# schematic.net
KiCad netlist of a schematic drawn in EasyEDA
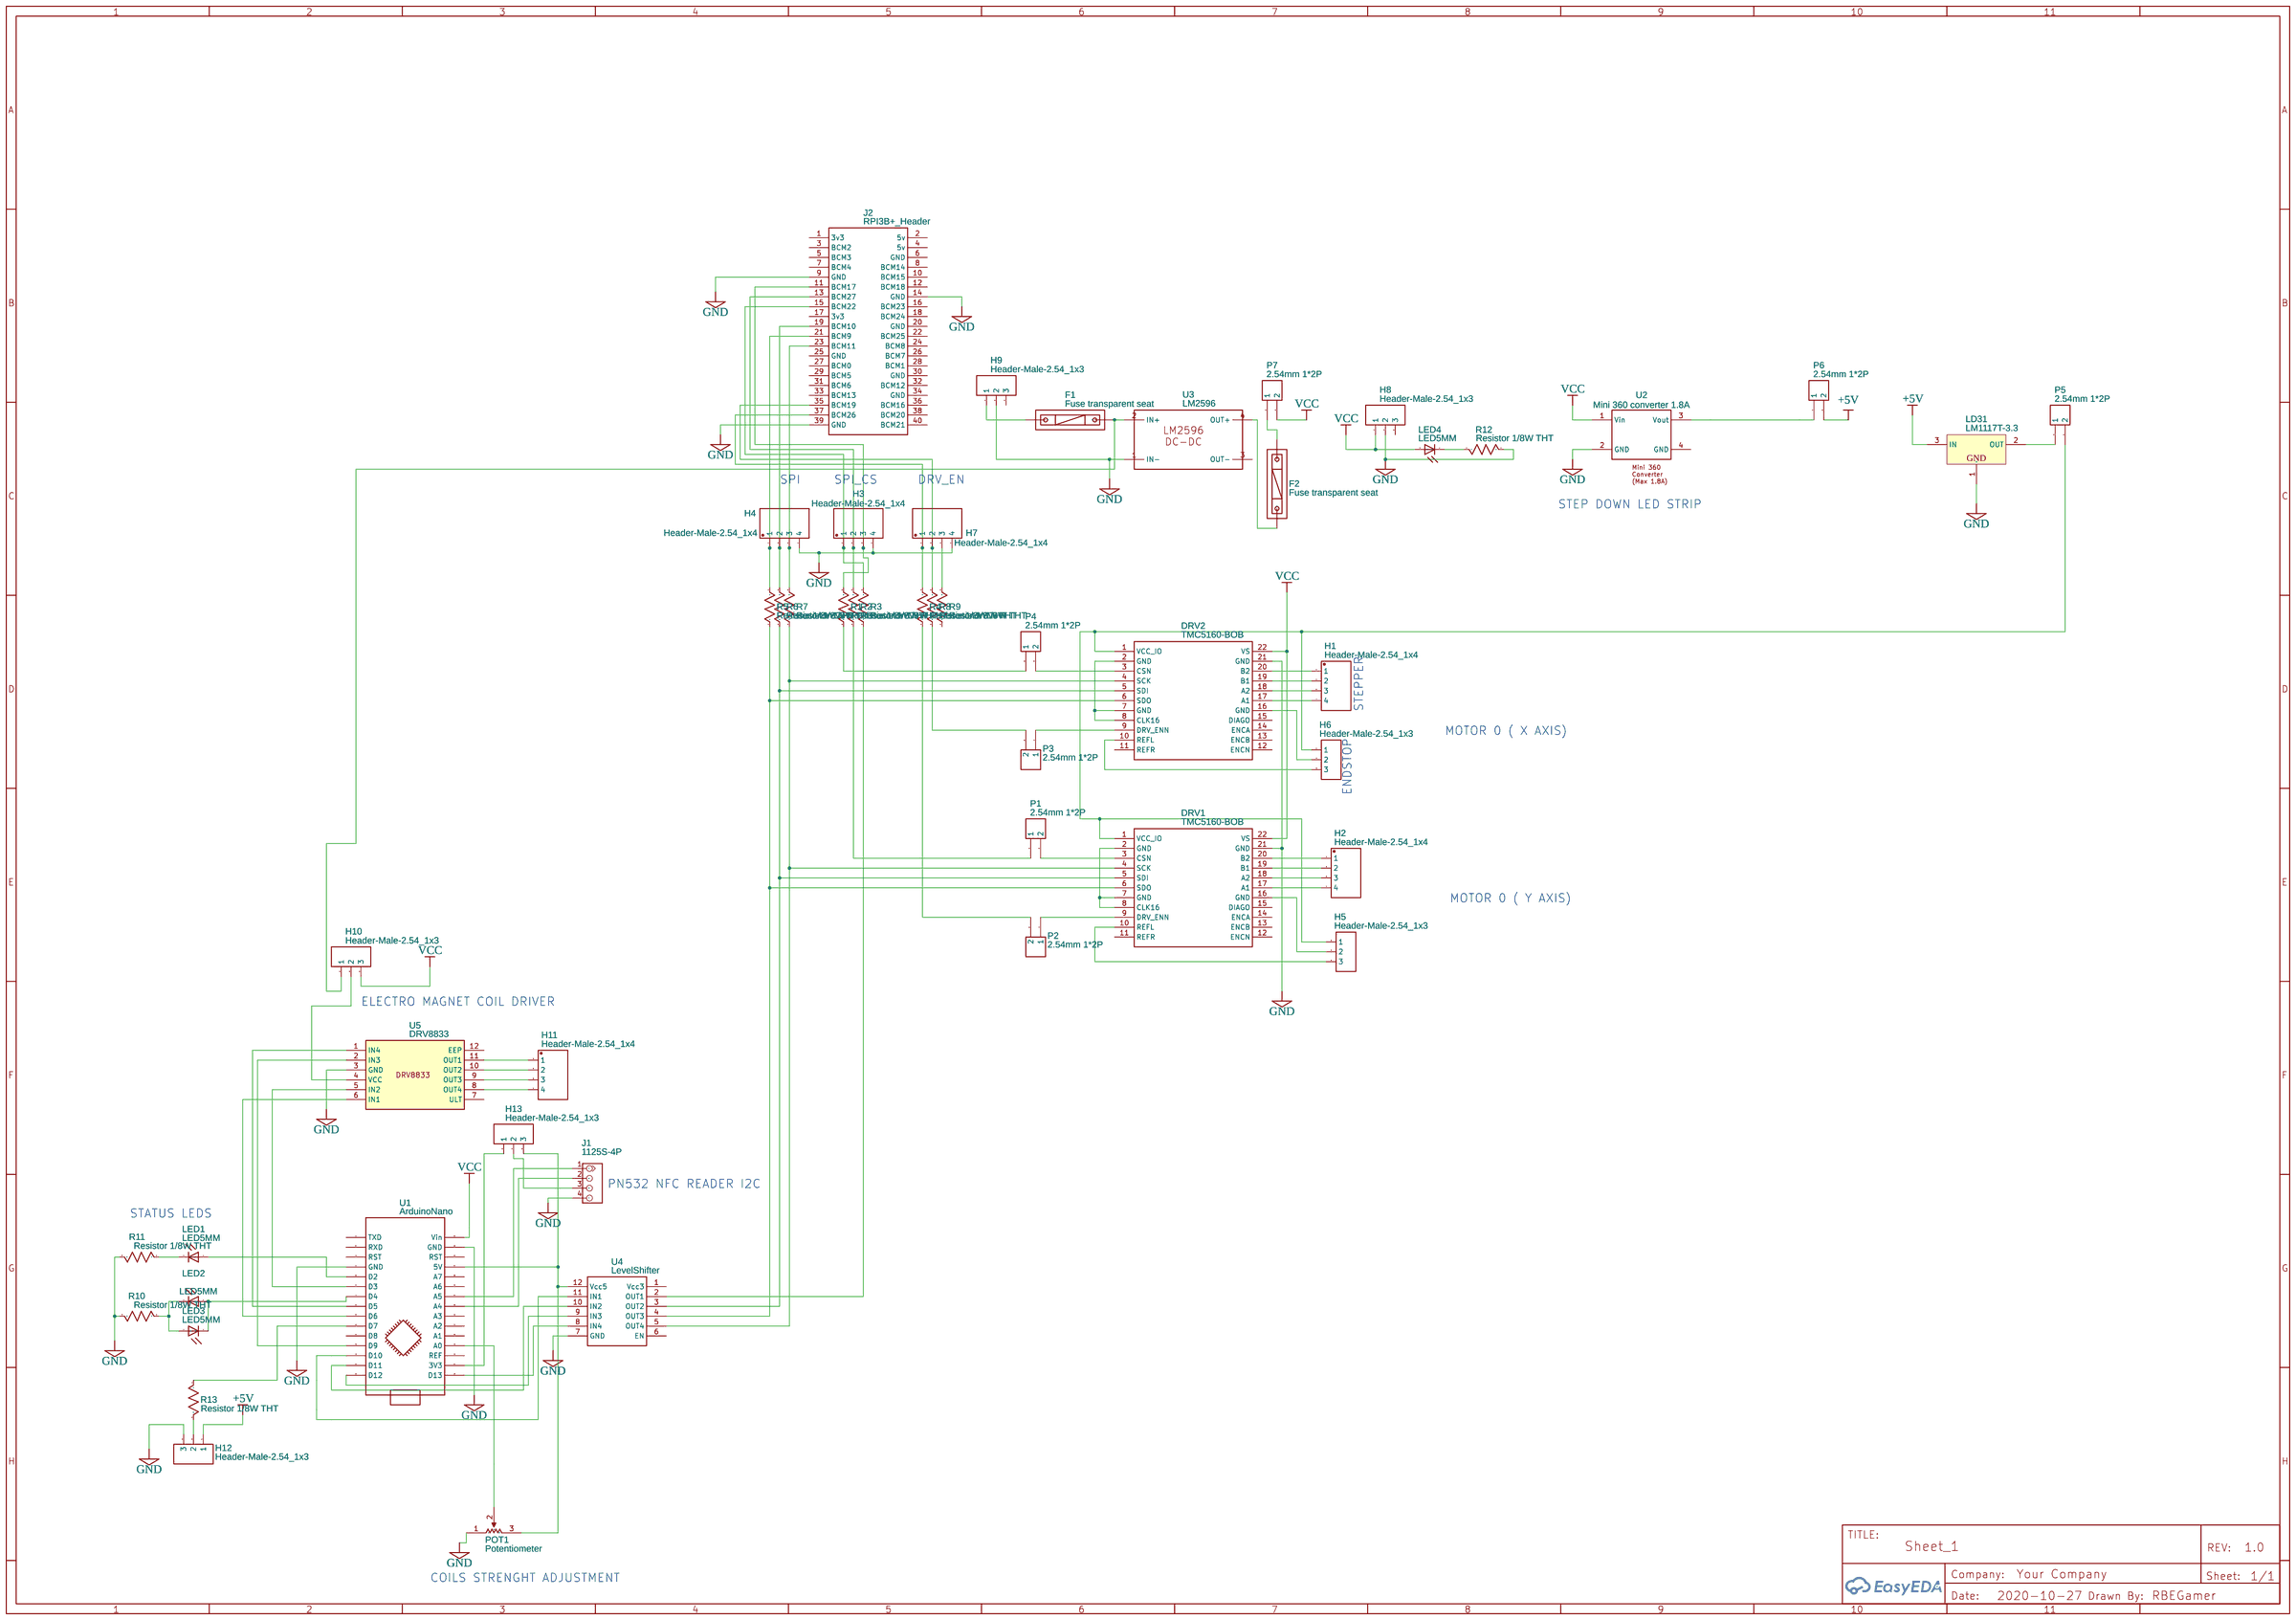
[diagram p0: schematic sheet]

(export (version "E")
  (design (tool "Eeschema 10.0.6"))
  (components
    (comp (ref "DRV1") (value "TMC5160-BOB") (libsource (lib "") (part "TMC5160-BOB")))
    (comp (ref "DRV2") (value "TMC5160-BOB") (libsource (lib "") (part "TMC5160-BOB")))
    (comp (ref "F1")
      (value "Fuse transparent seat")
      (fields (field (name "BOM_Supplier Part") "C58066"))
      (libsource (lib "") (part "Fuse transparent seat"))
    )
    (comp (ref "F2")
      (value "Fuse transparent seat")
      (fields (field (name "BOM_Supplier Part") "C58066"))
      (libsource (lib "") (part "Fuse transparent seat_1"))
    )
    (comp (ref "H1")
      (value "Header-Male-2.54_1x4")
      (fields
        (field (name "BOM_Manufacturer Part") "210S-1*4P L=11.6MMGold-plated black")
        (field (name "BOM_Supplier Part") "C124378")
      )
      (libsource (lib "") (part "Header-Male-2.54_1x4_1"))
    )
    (comp (ref "H2")
      (value "Header-Male-2.54_1x4")
      (fields
        (field (name "BOM_Manufacturer Part") "210S-1*4P L=11.6MMGold-plated black")
        (field (name "BOM_Supplier Part") "C124378")
      )
      (libsource (lib "") (part "Header-Male-2.54_1x4_1"))
    )
    (comp (ref "H3")
      (value "Header-Male-2.54_1x4")
      (fields
        (field (name "BOM_Manufacturer Part") "210S-1*4P L=11.6MMGold-plated black")
        (field (name "BOM_Supplier Part") "C124378")
      )
      (libsource (lib "") (part "Header-Male-2.54_1x4"))
    )
    (comp (ref "H4")
      (value "Header-Male-2.54_1x4")
      (fields
        (field (name "BOM_Manufacturer Part") "210S-1*4P L=11.6MMGold-plated black")
        (field (name "BOM_Supplier Part") "C124378")
      )
      (libsource (lib "") (part "Header-Male-2.54_1x4"))
    )
    (comp (ref "H5")
      (value "Header-Male-2.54_1x3")
      (fields
        (field (name "BOM_Manufacturer Part") "Header2.54mm 1*3P")
        (field (name "BOM_Supplier Part") "C49257")
      )
      (libsource (lib "") (part "Header-Male-2.54_1x3_1"))
    )
    (comp (ref "H6")
      (value "Header-Male-2.54_1x3")
      (fields
        (field (name "BOM_Manufacturer Part") "Header2.54mm 1*3P")
        (field (name "BOM_Supplier Part") "C49257")
      )
      (libsource (lib "") (part "Header-Male-2.54_1x3_1"))
    )
    (comp (ref "H7")
      (value "Header-Male-2.54_1x4")
      (fields
        (field (name "BOM_Manufacturer Part") "210S-1*4P L=11.6MMGold-plated black")
        (field (name "BOM_Supplier Part") "C124378")
      )
      (libsource (lib "") (part "Header-Male-2.54_1x4"))
    )
    (comp (ref "H8")
      (value "Header-Male-2.54_1x3")
      (fields
        (field (name "BOM_Manufacturer Part") "Header2.54mm 1*3P")
        (field (name "BOM_Supplier Part") "C49257")
      )
      (libsource (lib "") (part "Header-Male-2.54_1x3"))
    )
    (comp (ref "H9")
      (value "Header-Male-2.54_1x3")
      (fields
        (field (name "BOM_Manufacturer Part") "Header2.54mm 1*3P")
        (field (name "BOM_Supplier Part") "C49257")
      )
      (libsource (lib "") (part "Header-Male-2.54_1x3"))
    )
    (comp (ref "H10")
      (value "Header-Male-2.54_1x3")
      (fields
        (field (name "BOM_Manufacturer Part") "Header2.54mm 1*3P")
        (field (name "BOM_Supplier Part") "C49257")
      )
      (libsource (lib "") (part "Header-Male-2.54_1x3"))
    )
    (comp (ref "H11")
      (value "Header-Male-2.54_1x4")
      (fields
        (field (name "BOM_Manufacturer Part") "210S-1*4P L=11.6MMGold-plated black")
        (field (name "BOM_Supplier Part") "C124378")
      )
      (libsource (lib "") (part "Header-Male-2.54_1x4_1"))
    )
    (comp (ref "H12")
      (value "Header-Male-2.54_1x3")
      (fields
        (field (name "BOM_Manufacturer Part") "Header2.54mm 1*3P")
        (field (name "BOM_Supplier Part") "C49257")
      )
      (libsource (lib "") (part "Header-Male-2.54_1x3_2"))
    )
    (comp (ref "H13")
      (value "Header-Male-2.54_1x3")
      (fields
        (field (name "BOM_Manufacturer Part") "Header2.54mm 1*3P")
        (field (name "BOM_Supplier Part") "C49257")
      )
      (libsource (lib "") (part "Header-Male-2.54_1x3"))
    )
    (comp (ref "J1") (value "1125S-4P") (libsource (lib "") (part "1125S-4P")))
    (comp (ref "J2")
      (value "RPI3B+_Header")
      (fields
        (field (name "BOM_Manufacturer Part") "61304021121")
        (field (name "BOM_Supplier Part") "732-5310-ND")
      )
      (libsource (lib "") (part "RPI3B+_Header"))
    )
    (comp (ref "LD31") (value "LM1117T-3.3") (libsource (lib "") (part "LM1117T-3.3")))
    (comp (ref "LED1") (value "LED5MM") (libsource (lib "") (part "LED5MM")))
    (comp (ref "LED2") (value "LED5MM") (libsource (lib "") (part "LED5MM")))
    (comp (ref "LED3") (value "LED5MM") (libsource (lib "") (part "LED5MM_1")))
    (comp (ref "LED4") (value "LED5MM") (libsource (lib "") (part "LED5MM_1")))
    (comp (ref "P1")
      (value "2.54mm 1*2P")
      (fields (field (name "BOM_Supplier Part") "C36717"))
      (libsource (lib "") (part "2.54mm 1*2P_1"))
    )
    (comp (ref "P2")
      (value "2.54mm 1*2P")
      (fields (field (name "BOM_Supplier Part") "C36717"))
      (libsource (lib "") (part "2.54mm 1*2P"))
    )
    (comp (ref "P3")
      (value "2.54mm 1*2P")
      (fields (field (name "BOM_Supplier Part") "C36717"))
      (libsource (lib "") (part "2.54mm 1*2P"))
    )
    (comp (ref "P4")
      (value "2.54mm 1*2P")
      (fields (field (name "BOM_Supplier Part") "C36717"))
      (libsource (lib "") (part "2.54mm 1*2P_1"))
    )
    (comp (ref "P5")
      (value "2.54mm 1*2P")
      (fields (field (name "BOM_Supplier Part") "C36717"))
      (libsource (lib "") (part "2.54mm 1*2P_1"))
    )
    (comp (ref "P6")
      (value "2.54mm 1*2P")
      (fields (field (name "BOM_Supplier Part") "C36717"))
      (libsource (lib "") (part "2.54mm 1*2P_1"))
    )
    (comp (ref "P7")
      (value "2.54mm 1*2P")
      (fields (field (name "BOM_Supplier Part") "C36717"))
      (libsource (lib "") (part "2.54mm 1*2P_1"))
    )
    (comp (ref "POT1")
      (value "Potentiometer")
      (fields (field (name "BOM_Manufacturer Part") "potentiometer"))
      (libsource (lib "") (part "Potentiometer"))
    )
    (comp (ref "R1")
      (value "Resistor 1/8W THT")
      (fields (field (name "BOM_Manufacturer Part") "Generic"))
      (libsource (lib "") (part "Resistor 1/8W THT"))
    )
    (comp (ref "R2")
      (value "Resistor 1/8W THT")
      (fields (field (name "BOM_Manufacturer Part") "Generic"))
      (libsource (lib "") (part "Resistor 1/8W THT"))
    )
    (comp (ref "R3")
      (value "Resistor 1/8W THT")
      (fields (field (name "BOM_Manufacturer Part") "Generic"))
      (libsource (lib "") (part "Resistor 1/8W THT"))
    )
    (comp (ref "R4")
      (value "Resistor 1/8W THT")
      (fields (field (name "BOM_Manufacturer Part") "Generic"))
      (libsource (lib "") (part "Resistor 1/8W THT"))
    )
    (comp (ref "R5")
      (value "Resistor 1/8W THT")
      (fields (field (name "BOM_Manufacturer Part") "Generic"))
      (libsource (lib "") (part "Resistor 1/8W THT"))
    )
    (comp (ref "R6")
      (value "Resistor 1/8W THT")
      (fields (field (name "BOM_Manufacturer Part") "Generic"))
      (libsource (lib "") (part "Resistor 1/8W THT"))
    )
    (comp (ref "R7")
      (value "Resistor 1/8W THT")
      (fields (field (name "BOM_Manufacturer Part") "Generic"))
      (libsource (lib "") (part "Resistor 1/8W THT"))
    )
    (comp (ref "R8")
      (value "Resistor 1/8W THT")
      (fields (field (name "BOM_Manufacturer Part") "Generic"))
      (libsource (lib "") (part "Resistor 1/8W THT"))
    )
    (comp (ref "R9")
      (value "Resistor 1/8W THT")
      (fields (field (name "BOM_Manufacturer Part") "Generic"))
      (libsource (lib "") (part "Resistor 1/8W THT"))
    )
    (comp (ref "R10")
      (value "Resistor 1/8W THT")
      (fields (field (name "BOM_Manufacturer Part") "Generic"))
      (libsource (lib "") (part "Resistor 1/8W THT_1"))
    )
    (comp (ref "R11")
      (value "Resistor 1/8W THT")
      (fields (field (name "BOM_Manufacturer Part") "Generic"))
      (libsource (lib "") (part "Resistor 1/8W THT_1"))
    )
    (comp (ref "R12")
      (value "Resistor 1/8W THT")
      (fields (field (name "BOM_Manufacturer Part") "Generic"))
      (libsource (lib "") (part "Resistor 1/8W THT_3"))
    )
    (comp (ref "R13")
      (value "Resistor 1/8W THT")
      (fields (field (name "BOM_Manufacturer Part") "Generic"))
      (libsource (lib "") (part "Resistor 1/8W THT_2"))
    )
    (comp (ref "U1") (value "ArduinoNano") (libsource (lib "") (part "ArduinoNano")))
    (comp (ref "U2")
      (value "Mini 360 converter 1.8A")
      (fields (field (name "BOM_Manufacturer Part") "Mini 360 step down converter 1.8A"))
      (libsource (lib "") (part "Mini 360 converter 1.8A"))
    )
    (comp (ref "U3") (value "LM2596") (libsource (lib "") (part "LM2596")))
    (comp (ref "U4") (value "LevelShifter") (libsource (lib "") (part "LevelShifter")))
    (comp (ref "U5") (value "DRV8833") (libsource (lib "") (part "DRV8833")))
  )
  (nets
    (net (code "1") (name "+5V") (class "Default")
      (node (ref "H12") (pin "1") (pinfunction "1_1") (pintype "input"))
      (node (ref "LD31") (pin "3") (pinfunction "IN_3") (pintype "passive"))
      (node (ref "P6") (pin "2") (pinfunction "2_2") (pintype "input"))
    )
    (net (code "2") (name "GND") (class "Default")
      (node (ref "DRV1") (pin "21") (pinfunction "GND_21") (pintype "unspecified"))
      (node (ref "DRV2") (pin "21") (pinfunction "GND_21") (pintype "unspecified"))
      (node (ref "H12") (pin "3") (pinfunction "3_3") (pintype "input"))
      (node (ref "H3") (pin "4") (pinfunction "4_4") (pintype "unspecified"))
      (node (ref "H4") (pin "4") (pinfunction "4_4") (pintype "unspecified"))
      (node (ref "H7") (pin "4") (pinfunction "4_4") (pintype "unspecified"))
      (node (ref "H8") (pin "2") (pinfunction "2_2") (pintype "input"))
      (node (ref "H9") (pin "2") (pinfunction "2_2") (pintype "input"))
      (node (ref "J1") (pin "4") (pinfunction "4_4") (pintype "unspecified"))
      (node (ref "J2") (pin "14") (pinfunction "GND_14") (pintype "unspecified"))
      (node (ref "J2") (pin "39") (pinfunction "GND_39") (pintype "unspecified"))
      (node (ref "J2") (pin "9") (pinfunction "GND_9") (pintype "unspecified"))
      (node (ref "LD31") (pin "1") (pinfunction "GND_1") (pintype "passive"))
      (node (ref "POT1") (pin "1") (pinfunction "1_1") (pintype "unspecified"))
      (node (ref "R10") (pin "2") (pinfunction "2_2") (pintype "unspecified"))
      (node (ref "R11") (pin "2") (pinfunction "2_2") (pintype "unspecified"))
      (node (ref "R12") (pin "2") (pinfunction "2_2") (pintype "unspecified"))
      (node (ref "U1") (pin "29") (pinfunction "GND_29") (pintype "unspecified"))
      (node (ref "U1") (pin "4") (pinfunction "GND_4") (pintype "unspecified"))
      (node (ref "U2") (pin "2") (pinfunction "GND_2") (pintype "unspecified"))
      (node (ref "U3") (pin "1") (pinfunction "IN-_1") (pintype "unspecified"))
      (node (ref "U4") (pin "7") (pinfunction "GND_7") (pintype "unspecified"))
      (node (ref "U5") (pin "3") (pinfunction "GND_3") (pintype "unspecified"))
    )
    (net (code "3") (name "Net-(DRV1-A1)") (class "Default")
      (node (ref "DRV1") (pin "17") (pinfunction "A1_17") (pintype "unspecified"))
      (node (ref "H2") (pin "4") (pinfunction "4_4") (pintype "unspecified"))
    )
    (net (code "4") (name "Net-(DRV1-A2)") (class "Default")
      (node (ref "DRV1") (pin "18") (pinfunction "A2_18") (pintype "unspecified"))
      (node (ref "H2") (pin "3") (pinfunction "3_3") (pintype "unspecified"))
    )
    (net (code "5") (name "Net-(DRV1-B1)") (class "Default")
      (node (ref "DRV1") (pin "19") (pinfunction "B1_19") (pintype "unspecified"))
      (node (ref "H2") (pin "2") (pinfunction "2_2") (pintype "unspecified"))
    )
    (net (code "6") (name "Net-(DRV1-B2)") (class "Default")
      (node (ref "DRV1") (pin "20") (pinfunction "B2_20") (pintype "unspecified"))
      (node (ref "H2") (pin "1") (pinfunction "1_1") (pintype "unspecified"))
    )
    (net (code "7") (name "Net-(DRV1-CLK16)") (class "Default")
      (node (ref "DRV1") (pin "2") (pinfunction "GND_2") (pintype "unspecified"))
      (node (ref "DRV1") (pin "7") (pinfunction "GND_7") (pintype "unspecified"))
      (node (ref "DRV1") (pin "8") (pinfunction "CLK16_8") (pintype "unspecified"))
    )
    (net (code "8") (name "Net-(DRV1-CSN)") (class "Default")
      (node (ref "DRV1") (pin "3") (pinfunction "CSN_3") (pintype "unspecified"))
      (node (ref "P1") (pin "2") (pinfunction "2_2") (pintype "input"))
    )
    (net (code "9") (name "Net-(DRV1-DRV_ENN)") (class "Default")
      (node (ref "DRV1") (pin "9") (pinfunction "DRV_ENN_9") (pintype "unspecified"))
      (node (ref "P2") (pin "1") (pinfunction "1_1") (pintype "input"))
    )
    (net (code "10") (name "Net-(DRV1-GND-Pad16)") (class "Default")
      (node (ref "DRV1") (pin "16") (pinfunction "GND_16") (pintype "unspecified"))
      (node (ref "H5") (pin "2") (pinfunction "2_2") (pintype "input"))
    )
    (net (code "11") (name "Net-(DRV1-REFL)") (class "Default")
      (node (ref "DRV1") (pin "10") (pinfunction "REFL_10") (pintype "unspecified"))
      (node (ref "H5") (pin "3") (pinfunction "3_3") (pintype "input"))
    )
    (net (code "12") (name "Net-(DRV1-SCK)") (class "Default")
      (node (ref "DRV1") (pin "4") (pinfunction "SCK_4") (pintype "unspecified"))
      (node (ref "DRV2") (pin "4") (pinfunction "SCK_4") (pintype "unspecified"))
      (node (ref "R7") (pin "1") (pinfunction "1_1") (pintype "unspecified"))
      (node (ref "U4") (pin "5") (pinfunction "OUT4_5") (pintype "unspecified"))
    )
    (net (code "13") (name "Net-(DRV1-SDI)") (class "Default")
      (node (ref "DRV1") (pin "5") (pinfunction "SDI_5") (pintype "unspecified"))
      (node (ref "DRV2") (pin "5") (pinfunction "SDI_5") (pintype "unspecified"))
      (node (ref "R6") (pin "1") (pinfunction "1_1") (pintype "unspecified"))
      (node (ref "U4") (pin "3") (pinfunction "OUT2_3") (pintype "unspecified"))
    )
    (net (code "14") (name "Net-(DRV1-SDO)") (class "Default")
      (node (ref "DRV1") (pin "6") (pinfunction "SDO_6") (pintype "unspecified"))
      (node (ref "DRV2") (pin "6") (pinfunction "SDO_6") (pintype "unspecified"))
      (node (ref "R5") (pin "1") (pinfunction "1_1") (pintype "unspecified"))
      (node (ref "U4") (pin "4") (pinfunction "OUT3_4") (pintype "unspecified"))
    )
    (net (code "15") (name "Net-(DRV1-VCC_IO)") (class "Default")
      (node (ref "DRV1") (pin "1") (pinfunction "VCC_IO_1") (pintype "unspecified"))
      (node (ref "DRV2") (pin "1") (pinfunction "VCC_IO_1") (pintype "unspecified"))
      (node (ref "H5") (pin "1") (pinfunction "1_1") (pintype "input"))
      (node (ref "H6") (pin "1") (pinfunction "1_1") (pintype "input"))
      (node (ref "P5") (pin "2") (pinfunction "2_2") (pintype "input"))
    )
    (net (code "16") (name "Net-(DRV2-A1)") (class "Default")
      (node (ref "DRV2") (pin "17") (pinfunction "A1_17") (pintype "unspecified"))
      (node (ref "H1") (pin "4") (pinfunction "4_4") (pintype "unspecified"))
    )
    (net (code "17") (name "Net-(DRV2-A2)") (class "Default")
      (node (ref "DRV2") (pin "18") (pinfunction "A2_18") (pintype "unspecified"))
      (node (ref "H1") (pin "3") (pinfunction "3_3") (pintype "unspecified"))
    )
    (net (code "18") (name "Net-(DRV2-B1)") (class "Default")
      (node (ref "DRV2") (pin "19") (pinfunction "B1_19") (pintype "unspecified"))
      (node (ref "H1") (pin "2") (pinfunction "2_2") (pintype "unspecified"))
    )
    (net (code "19") (name "Net-(DRV2-B2)") (class "Default")
      (node (ref "DRV2") (pin "20") (pinfunction "B2_20") (pintype "unspecified"))
      (node (ref "H1") (pin "1") (pinfunction "1_1") (pintype "unspecified"))
    )
    (net (code "20") (name "Net-(DRV2-CLK16)") (class "Default")
      (node (ref "DRV2") (pin "2") (pinfunction "GND_2") (pintype "unspecified"))
      (node (ref "DRV2") (pin "7") (pinfunction "GND_7") (pintype "unspecified"))
      (node (ref "DRV2") (pin "8") (pinfunction "CLK16_8") (pintype "unspecified"))
    )
    (net (code "21") (name "Net-(DRV2-CSN)") (class "Default")
      (node (ref "DRV2") (pin "3") (pinfunction "CSN_3") (pintype "unspecified"))
      (node (ref "P4") (pin "2") (pinfunction "2_2") (pintype "input"))
    )
    (net (code "22") (name "Net-(DRV2-DRV_ENN)") (class "Default")
      (node (ref "DRV2") (pin "9") (pinfunction "DRV_ENN_9") (pintype "unspecified"))
      (node (ref "P3") (pin "1") (pinfunction "1_1") (pintype "input"))
    )
    (net (code "23") (name "Net-(DRV2-GND-Pad16)") (class "Default")
      (node (ref "DRV2") (pin "16") (pinfunction "GND_16") (pintype "unspecified"))
      (node (ref "H6") (pin "2") (pinfunction "2_2") (pintype "input"))
    )
    (net (code "24") (name "Net-(DRV2-REFL)") (class "Default")
      (node (ref "DRV2") (pin "10") (pinfunction "REFL_10") (pintype "unspecified"))
      (node (ref "H6") (pin "3") (pinfunction "3_3") (pintype "input"))
    )
    (net (code "25") (name "Net-(F1-Pad1)") (class "Default")
      (node (ref "F1") (pin "1") (pinfunction "1_1") (pintype "unspecified"))
      (node (ref "H9") (pin "1") (pinfunction "1_1") (pintype "input"))
    )
    (net (code "26") (name "Net-(F2-Pad2)") (class "Default")
      (node (ref "F2") (pin "2") (pinfunction "2_2") (pintype "unspecified"))
      (node (ref "P7") (pin "1") (pinfunction "1_1") (pintype "input"))
    )
    (net (code "27") (name "Net-(H7-Pad3)") (class "Default")
      (node (ref "H7") (pin "3") (pinfunction "3_3") (pintype "unspecified"))
      (node (ref "R9") (pin "2") (pinfunction "2_2") (pintype "unspecified"))
    )
    (net (code "28") (name "Net-(H12-Pad2)") (class "Default")
      (node (ref "H12") (pin "2") (pinfunction "2_2") (pintype "input"))
      (node (ref "R13") (pin "2") (pinfunction "2_2") (pintype "unspecified"))
    )
    (net (code "29") (name "Net-(H13-Pad2)") (class "Default")
      (node (ref "H13") (pin "2") (pinfunction "2_2") (pintype "input"))
      (node (ref "J1") (pin "3") (pinfunction "3_3") (pintype "unspecified"))
    )
    (net (code "30") (name "Net-(J2-BCM9)") (class "Default")
      (node (ref "H4") (pin "1") (pinfunction "1_1") (pintype "unspecified"))
      (node (ref "J2") (pin "21") (pinfunction "BCM9_21") (pintype "unspecified"))
      (node (ref "R5") (pin "2") (pinfunction "2_2") (pintype "unspecified"))
    )
    (net (code "31") (name "Net-(J2-BCM10)") (class "Default")
      (node (ref "H4") (pin "2") (pinfunction "2_2") (pintype "unspecified"))
      (node (ref "J2") (pin "19") (pinfunction "BCM10_19") (pintype "unspecified"))
      (node (ref "R6") (pin "2") (pinfunction "2_2") (pintype "unspecified"))
    )
    (net (code "32") (name "Net-(J2-BCM11)") (class "Default")
      (node (ref "H4") (pin "3") (pinfunction "3_3") (pintype "unspecified"))
      (node (ref "J2") (pin "23") (pinfunction "BCM11_23") (pintype "unspecified"))
      (node (ref "R7") (pin "2") (pinfunction "2_2") (pintype "unspecified"))
    )
    (net (code "33") (name "Net-(J2-BCM17)") (class "Default")
      (node (ref "H3") (pin "3") (pinfunction "3_3") (pintype "unspecified"))
      (node (ref "J2") (pin "11") (pinfunction "BCM17_11") (pintype "unspecified"))
      (node (ref "R1") (pin "2") (pinfunction "2_2") (pintype "unspecified"))
    )
    (net (code "34") (name "Net-(J2-BCM19)") (class "Default")
      (node (ref "H7") (pin "2") (pinfunction "2_2") (pintype "unspecified"))
      (node (ref "J2") (pin "35") (pinfunction "BCM19_35") (pintype "unspecified"))
      (node (ref "R8") (pin "2") (pinfunction "2_2") (pintype "unspecified"))
    )
    (net (code "35") (name "Net-(J2-BCM22)") (class "Default")
      (node (ref "H3") (pin "1") (pinfunction "1_1") (pintype "unspecified"))
      (node (ref "J2") (pin "15") (pinfunction "BCM22_15") (pintype "unspecified"))
      (node (ref "R3") (pin "2") (pinfunction "2_2") (pintype "unspecified"))
    )
    (net (code "36") (name "Net-(J2-BCM26)") (class "Default")
      (node (ref "H7") (pin "1") (pinfunction "1_1") (pintype "unspecified"))
      (node (ref "J2") (pin "37") (pinfunction "BCM26_37") (pintype "unspecified"))
      (node (ref "R4") (pin "2") (pinfunction "2_2") (pintype "unspecified"))
    )
    (net (code "37") (name "Net-(J2-BCM27)") (class "Default")
      (node (ref "H3") (pin "2") (pinfunction "2_2") (pintype "unspecified"))
      (node (ref "J2") (pin "13") (pinfunction "BCM27_13") (pintype "unspecified"))
      (node (ref "R2") (pin "2") (pinfunction "2_2") (pintype "unspecified"))
    )
    (net (code "38") (name "Net-(LD31-OUT)") (class "Default")
      (node (ref "LD31") (pin "2") (pinfunction "OUT_2") (pintype "passive"))
      (node (ref "P5") (pin "1") (pinfunction "1_1") (pintype "input"))
    )
    (net (code "39") (name "Net-(LED1-C)") (class "Default")
      (node (ref "LED1") (pin "K") (pinfunction "C_K") (pintype "unspecified"))
      (node (ref "R11") (pin "1") (pinfunction "1_1") (pintype "unspecified"))
    )
    (net (code "40") (name "Net-(LED2-C)") (class "Default")
      (node (ref "LED2") (pin "K") (pinfunction "C_K") (pintype "unspecified"))
      (node (ref "LED3") (pin "A") (pinfunction "A_A") (pintype "unspecified"))
      (node (ref "R10") (pin "1") (pinfunction "1_1") (pintype "unspecified"))
    )
    (net (code "41") (name "Net-(LED3-C)") (class "Default")
      (node (ref "LED2") (pin "A") (pinfunction "A_A") (pintype "unspecified"))
      (node (ref "LED3") (pin "K") (pinfunction "C_K") (pintype "unspecified"))
      (node (ref "U1") (pin "7") (pinfunction "D4_7") (pintype "unspecified"))
    )
    (net (code "42") (name "Net-(LED4-C)") (class "Default")
      (node (ref "LED4") (pin "K") (pinfunction "C_K") (pintype "unspecified"))
      (node (ref "R12") (pin "1") (pinfunction "1_1") (pintype "unspecified"))
    )
    (net (code "43") (name "Net-(P1-Pad1)") (class "Default")
      (node (ref "P1") (pin "1") (pinfunction "1_1") (pintype "input"))
      (node (ref "R2") (pin "1") (pinfunction "1_1") (pintype "unspecified"))
    )
    (net (code "44") (name "Net-(P2-Pad2)") (class "Default")
      (node (ref "P2") (pin "2") (pinfunction "2_2") (pintype "input"))
      (node (ref "R4") (pin "1") (pinfunction "1_1") (pintype "unspecified"))
    )
    (net (code "45") (name "Net-(P3-Pad2)") (class "Default")
      (node (ref "P3") (pin "2") (pinfunction "2_2") (pintype "input"))
      (node (ref "R8") (pin "1") (pinfunction "1_1") (pintype "unspecified"))
    )
    (net (code "46") (name "Net-(P4-Pad1)") (class "Default")
      (node (ref "P4") (pin "1") (pinfunction "1_1") (pintype "input"))
      (node (ref "R1") (pin "1") (pinfunction "1_1") (pintype "unspecified"))
    )
    (net (code "47") (name "Net-(U1-3V3)") (class "Default")
      (node (ref "H13") (pin "1") (pinfunction "1_1") (pintype "input"))
      (node (ref "U1") (pin "17") (pinfunction "3V3_17") (pintype "unspecified"))
    )
    (net (code "48") (name "Net-(U1-5V)") (class "Default")
      (node (ref "H13") (pin "3") (pinfunction "3_3") (pintype "input"))
      (node (ref "POT1") (pin "3") (pinfunction "3_3") (pintype "unspecified"))
      (node (ref "U1") (pin "27") (pinfunction "5V_27") (pintype "unspecified"))
      (node (ref "U4") (pin "12") (pinfunction "Vcc5_12") (pintype "unspecified"))
    )
    (net (code "49") (name "Net-(U1-A0)") (class "Default")
      (node (ref "POT1") (pin "2") (pinfunction "2_2") (pintype "unspecified"))
      (node (ref "U1") (pin "19") (pinfunction "A0_19") (pintype "unspecified"))
    )
    (net (code "50") (name "Net-(U1-A4)") (class "Default")
      (node (ref "J1") (pin "2") (pinfunction "2_2") (pintype "unspecified"))
      (node (ref "U1") (pin "23") (pinfunction "A4_23") (pintype "unspecified"))
    )
    (net (code "51") (name "Net-(U1-A5)") (class "Default")
      (node (ref "J1") (pin "1") (pinfunction "1_1") (pintype "unspecified"))
      (node (ref "U1") (pin "24") (pinfunction "A5_24") (pintype "unspecified"))
    )
    (net (code "52") (name "Net-(U1-D2)") (class "Default")
      (node (ref "LED1") (pin "A") (pinfunction "A_A") (pintype "unspecified"))
      (node (ref "U1") (pin "5") (pinfunction "D2_5") (pintype "unspecified"))
    )
    (net (code "53") (name "Net-(U1-D3)") (class "Default")
      (node (ref "U1") (pin "6") (pinfunction "D3_6") (pintype "unspecified"))
      (node (ref "U5") (pin "5") (pinfunction "IN2_5") (pintype "unspecified"))
    )
    (net (code "54") (name "Net-(U1-D5)") (class "Default")
      (node (ref "U1") (pin "8") (pinfunction "D5_8") (pintype "unspecified"))
      (node (ref "U5") (pin "1") (pinfunction "IN4_1") (pintype "unspecified"))
    )
    (net (code "55") (name "Net-(U1-D6)") (class "Default")
      (node (ref "U1") (pin "9") (pinfunction "D6_9") (pintype "unspecified"))
      (node (ref "U5") (pin "6") (pinfunction "IN1_6") (pintype "unspecified"))
    )
    (net (code "56") (name "Net-(U1-D7)") (class "Default")
      (node (ref "R13") (pin "1") (pinfunction "1_1") (pintype "unspecified"))
      (node (ref "U1") (pin "10") (pinfunction "D7_10") (pintype "unspecified"))
    )
    (net (code "57") (name "Net-(U1-D9)") (class "Default")
      (node (ref "U1") (pin "12") (pinfunction "D9_12") (pintype "unspecified"))
      (node (ref "U5") (pin "2") (pinfunction "IN3_2") (pintype "unspecified"))
    )
    (net (code "58") (name "Net-(U1-D10)") (class "Default")
      (node (ref "U1") (pin "13") (pinfunction "D10_13") (pintype "unspecified"))
      (node (ref "U4") (pin "11") (pinfunction "IN1_11") (pintype "unspecified"))
    )
    (net (code "59") (name "Net-(U1-D11)") (class "Default")
      (node (ref "U1") (pin "14") (pinfunction "D11_14") (pintype "unspecified"))
      (node (ref "U4") (pin "10") (pinfunction "IN2_10") (pintype "unspecified"))
    )
    (net (code "60") (name "Net-(U1-D12)") (class "Default")
      (node (ref "U1") (pin "15") (pinfunction "D12_15") (pintype "unspecified"))
      (node (ref "U4") (pin "9") (pinfunction "IN3_9") (pintype "unspecified"))
    )
    (net (code "61") (name "Net-(U1-D13)") (class "Default")
      (node (ref "U1") (pin "16") (pinfunction "D13_16") (pintype "unspecified"))
      (node (ref "U4") (pin "8") (pinfunction "IN4_8") (pintype "unspecified"))
    )
    (net (code "62") (name "Net-(U2-Vout)") (class "Default")
      (node (ref "P6") (pin "1") (pinfunction "1_1") (pintype "input"))
      (node (ref "U2") (pin "3") (pinfunction "Vout_3") (pintype "unspecified"))
    )
    (net (code "63") (name "Net-(U3-IN+)") (class "Default")
      (node (ref "F1") (pin "2") (pinfunction "2_2") (pintype "unspecified"))
      (node (ref "H10") (pin "1") (pinfunction "1_1") (pintype "input"))
      (node (ref "U3") (pin "2") (pinfunction "IN+_2") (pintype "unspecified"))
    )
    (net (code "64") (name "Net-(U3-OUT+)") (class "Default")
      (node (ref "F2") (pin "1") (pinfunction "1_1") (pintype "unspecified"))
      (node (ref "U3") (pin "4") (pinfunction "OUT+_4") (pintype "unspecified"))
    )
    (net (code "65") (name "Net-(U4-OUT1)") (class "Default")
      (node (ref "R3") (pin "1") (pinfunction "1_1") (pintype "unspecified"))
      (node (ref "U4") (pin "2") (pinfunction "OUT1_2") (pintype "unspecified"))
    )
    (net (code "66") (name "Net-(U5-OUT1)") (class "Default")
      (node (ref "H11") (pin "1") (pinfunction "1_1") (pintype "unspecified"))
      (node (ref "U5") (pin "11") (pinfunction "OUT1_11") (pintype "unspecified"))
    )
    (net (code "67") (name "Net-(U5-OUT2)") (class "Default")
      (node (ref "H11") (pin "2") (pinfunction "2_2") (pintype "unspecified"))
      (node (ref "U5") (pin "10") (pinfunction "OUT2_10") (pintype "unspecified"))
    )
    (net (code "68") (name "Net-(U5-OUT3)") (class "Default")
      (node (ref "H11") (pin "3") (pinfunction "3_3") (pintype "unspecified"))
      (node (ref "U5") (pin "9") (pinfunction "OUT3_9") (pintype "unspecified"))
    )
    (net (code "69") (name "Net-(U5-OUT4)") (class "Default")
      (node (ref "H11") (pin "4") (pinfunction "4_4") (pintype "unspecified"))
      (node (ref "U5") (pin "8") (pinfunction "OUT4_8") (pintype "unspecified"))
    )
    (net (code "70") (name "Net-(U5-VCC)") (class "Default")
      (node (ref "H10") (pin "2") (pinfunction "2_2") (pintype "input"))
      (node (ref "U5") (pin "4") (pinfunction "VCC_4") (pintype "unspecified"))
    )
    (net (code "71") (name "VCC") (class "Default")
      (node (ref "DRV1") (pin "22") (pinfunction "VS_22") (pintype "unspecified"))
      (node (ref "DRV2") (pin "22") (pinfunction "VS_22") (pintype "unspecified"))
      (node (ref "H10") (pin "3") (pinfunction "3_3") (pintype "input"))
      (node (ref "H8") (pin "1") (pinfunction "1_1") (pintype "input"))
      (node (ref "LED4") (pin "A") (pinfunction "A_A") (pintype "unspecified"))
      (node (ref "P7") (pin "2") (pinfunction "2_2") (pintype "input"))
      (node (ref "U1") (pin "30") (pinfunction "Vin_30") (pintype "unspecified"))
      (node (ref "U2") (pin "1") (pinfunction "Vin_1") (pintype "unspecified"))
    )
    (net (code "72") (name "unconnected-(DRV1-DIAGO-Pad15)") (class "Default")
      (node (ref "DRV1") (pin "15") (pinfunction "DIAGO_15") (pintype "unspecified"))
    )
    (net (code "73") (name "unconnected-(DRV1-ENCA-Pad14)") (class "Default")
      (node (ref "DRV1") (pin "14") (pinfunction "ENCA_14") (pintype "unspecified"))
    )
    (net (code "74") (name "unconnected-(DRV1-ENCB-Pad13)") (class "Default")
      (node (ref "DRV1") (pin "13") (pinfunction "ENCB_13") (pintype "unspecified"))
    )
    (net (code "75") (name "unconnected-(DRV1-ENCN-Pad12)") (class "Default")
      (node (ref "DRV1") (pin "12") (pinfunction "ENCN_12") (pintype "unspecified"))
    )
    (net (code "76") (name "unconnected-(DRV1-REFR-Pad11)") (class "Default")
      (node (ref "DRV1") (pin "11") (pinfunction "REFR_11") (pintype "unspecified"))
    )
    (net (code "77") (name "unconnected-(DRV2-DIAGO-Pad15)") (class "Default")
      (node (ref "DRV2") (pin "15") (pinfunction "DIAGO_15") (pintype "unspecified"))
    )
    (net (code "78") (name "unconnected-(DRV2-ENCA-Pad14)") (class "Default")
      (node (ref "DRV2") (pin "14") (pinfunction "ENCA_14") (pintype "unspecified"))
    )
    (net (code "79") (name "unconnected-(DRV2-ENCB-Pad13)") (class "Default")
      (node (ref "DRV2") (pin "13") (pinfunction "ENCB_13") (pintype "unspecified"))
    )
    (net (code "80") (name "unconnected-(DRV2-ENCN-Pad12)") (class "Default")
      (node (ref "DRV2") (pin "12") (pinfunction "ENCN_12") (pintype "unspecified"))
    )
    (net (code "81") (name "unconnected-(DRV2-REFR-Pad11)") (class "Default")
      (node (ref "DRV2") (pin "11") (pinfunction "REFR_11") (pintype "unspecified"))
    )
    (net (code "82") (name "unconnected-(H8-Pad3)") (class "Default")
      (node (ref "H8") (pin "3") (pinfunction "3_3") (pintype "input"))
    )
    (net (code "83") (name "unconnected-(H9-Pad3)") (class "Default")
      (node (ref "H9") (pin "3") (pinfunction "3_3") (pintype "input"))
    )
    (net (code "84") (name "unconnected-(J2-3v3-Pad1)") (class "Default")
      (node (ref "J2") (pin "1") (pinfunction "3v3_1") (pintype "unspecified"))
    )
    (net (code "85") (name "unconnected-(J2-3v3-Pad17)") (class "Default")
      (node (ref "J2") (pin "17") (pinfunction "3v3_17") (pintype "unspecified"))
    )
    (net (code "86") (name "unconnected-(J2-5v-Pad2)") (class "Default")
      (node (ref "J2") (pin "2") (pinfunction "5v_2") (pintype "unspecified"))
    )
    (net (code "87") (name "unconnected-(J2-5v-Pad4)") (class "Default")
      (node (ref "J2") (pin "4") (pinfunction "5v_4") (pintype "unspecified"))
    )
    (net (code "88") (name "unconnected-(J2-BCM0-Pad27)") (class "Default")
      (node (ref "J2") (pin "27") (pinfunction "BCM0_27") (pintype "unspecified"))
    )
    (net (code "89") (name "unconnected-(J2-BCM1-Pad28)") (class "Default")
      (node (ref "J2") (pin "28") (pinfunction "BCM1_28") (pintype "unspecified"))
    )
    (net (code "90") (name "unconnected-(J2-BCM2-Pad3)") (class "Default")
      (node (ref "J2") (pin "3") (pinfunction "BCM2_3") (pintype "unspecified"))
    )
    (net (code "91") (name "unconnected-(J2-BCM3-Pad5)") (class "Default")
      (node (ref "J2") (pin "5") (pinfunction "BCM3_5") (pintype "unspecified"))
    )
    (net (code "92") (name "unconnected-(J2-BCM4-Pad7)") (class "Default")
      (node (ref "J2") (pin "7") (pinfunction "BCM4_7") (pintype "unspecified"))
    )
    (net (code "93") (name "unconnected-(J2-BCM5-Pad29)") (class "Default")
      (node (ref "J2") (pin "29") (pinfunction "BCM5_29") (pintype "unspecified"))
    )
    (net (code "94") (name "unconnected-(J2-BCM6-Pad31)") (class "Default")
      (node (ref "J2") (pin "31") (pinfunction "BCM6_31") (pintype "unspecified"))
    )
    (net (code "95") (name "unconnected-(J2-BCM7-Pad26)") (class "Default")
      (node (ref "J2") (pin "26") (pinfunction "BCM7_26") (pintype "unspecified"))
    )
    (net (code "96") (name "unconnected-(J2-BCM8-Pad24)") (class "Default")
      (node (ref "J2") (pin "24") (pinfunction "BCM8_24") (pintype "unspecified"))
    )
    (net (code "97") (name "unconnected-(J2-BCM12-Pad32)") (class "Default")
      (node (ref "J2") (pin "32") (pinfunction "BCM12_32") (pintype "unspecified"))
    )
    (net (code "98") (name "unconnected-(J2-BCM13-Pad33)") (class "Default")
      (node (ref "J2") (pin "33") (pinfunction "BCM13_33") (pintype "unspecified"))
    )
    (net (code "99") (name "unconnected-(J2-BCM14-Pad8)") (class "Default")
      (node (ref "J2") (pin "8") (pinfunction "BCM14_8") (pintype "unspecified"))
    )
    (net (code "100") (name "unconnected-(J2-BCM15-Pad10)") (class "Default")
      (node (ref "J2") (pin "10") (pinfunction "BCM15_10") (pintype "unspecified"))
    )
    (net (code "101") (name "unconnected-(J2-BCM16-Pad36)") (class "Default")
      (node (ref "J2") (pin "36") (pinfunction "BCM16_36") (pintype "unspecified"))
    )
    (net (code "102") (name "unconnected-(J2-BCM18-Pad12)") (class "Default")
      (node (ref "J2") (pin "12") (pinfunction "BCM18_12") (pintype "unspecified"))
    )
    (net (code "103") (name "unconnected-(J2-BCM20-Pad38)") (class "Default")
      (node (ref "J2") (pin "38") (pinfunction "BCM20_38") (pintype "unspecified"))
    )
    (net (code "104") (name "unconnected-(J2-BCM21-Pad40)") (class "Default")
      (node (ref "J2") (pin "40") (pinfunction "BCM21_40") (pintype "unspecified"))
    )
    (net (code "105") (name "unconnected-(J2-BCM23-Pad16)") (class "Default")
      (node (ref "J2") (pin "16") (pinfunction "BCM23_16") (pintype "unspecified"))
    )
    (net (code "106") (name "unconnected-(J2-BCM24-Pad18)") (class "Default")
      (node (ref "J2") (pin "18") (pinfunction "BCM24_18") (pintype "unspecified"))
    )
    (net (code "107") (name "unconnected-(J2-BCM25-Pad22)") (class "Default")
      (node (ref "J2") (pin "22") (pinfunction "BCM25_22") (pintype "unspecified"))
    )
    (net (code "108") (name "unconnected-(J2-GND-Pad6)") (class "Default")
      (node (ref "J2") (pin "6") (pinfunction "GND_6") (pintype "unspecified"))
    )
    (net (code "109") (name "unconnected-(J2-GND-Pad20)") (class "Default")
      (node (ref "J2") (pin "20") (pinfunction "GND_20") (pintype "unspecified"))
    )
    (net (code "110") (name "unconnected-(J2-GND-Pad25)") (class "Default")
      (node (ref "J2") (pin "25") (pinfunction "GND_25") (pintype "unspecified"))
    )
    (net (code "111") (name "unconnected-(J2-GND-Pad30)") (class "Default")
      (node (ref "J2") (pin "30") (pinfunction "GND_30") (pintype "unspecified"))
    )
    (net (code "112") (name "unconnected-(J2-GND-Pad34)") (class "Default")
      (node (ref "J2") (pin "34") (pinfunction "GND_34") (pintype "unspecified"))
    )
    (net (code "113") (name "unconnected-(R9-Pad1)") (class "Default")
      (node (ref "R9") (pin "1") (pinfunction "1_1") (pintype "unspecified"))
    )
    (net (code "114") (name "unconnected-(U1-A1-Pad20)") (class "Default")
      (node (ref "U1") (pin "20") (pinfunction "A1_20") (pintype "unspecified"))
    )
    (net (code "115") (name "unconnected-(U1-A2-Pad21)") (class "Default")
      (node (ref "U1") (pin "21") (pinfunction "A2_21") (pintype "unspecified"))
    )
    (net (code "116") (name "unconnected-(U1-A3-Pad22)") (class "Default")
      (node (ref "U1") (pin "22") (pinfunction "A3_22") (pintype "unspecified"))
    )
    (net (code "117") (name "unconnected-(U1-A6-Pad25)") (class "Default")
      (node (ref "U1") (pin "25") (pinfunction "A6_25") (pintype "unspecified"))
    )
    (net (code "118") (name "unconnected-(U1-A7-Pad26)") (class "Default")
      (node (ref "U1") (pin "26") (pinfunction "A7_26") (pintype "unspecified"))
    )
    (net (code "119") (name "unconnected-(U1-D8-Pad11)") (class "Default")
      (node (ref "U1") (pin "11") (pinfunction "D8_11") (pintype "unspecified"))
    )
    (net (code "120") (name "unconnected-(U1-REF-Pad18)") (class "Default")
      (node (ref "U1") (pin "18") (pinfunction "REF_18") (pintype "unspecified"))
    )
    (net (code "121") (name "unconnected-(U1-RST-Pad3)") (class "Default")
      (node (ref "U1") (pin "3") (pinfunction "RST_3") (pintype "unspecified"))
    )
    (net (code "122") (name "unconnected-(U1-RST-Pad28)") (class "Default")
      (node (ref "U1") (pin "28") (pinfunction "RST_28") (pintype "unspecified"))
    )
    (net (code "123") (name "unconnected-(U1-RXD-Pad2)") (class "Default")
      (node (ref "U1") (pin "2") (pinfunction "RXD_2") (pintype "unspecified"))
    )
    (net (code "124") (name "unconnected-(U1-TXD-Pad1)") (class "Default")
      (node (ref "U1") (pin "1") (pinfunction "TXD_1") (pintype "unspecified"))
    )
    (net (code "125") (name "unconnected-(U2-GND-Pad4)") (class "Default")
      (node (ref "U2") (pin "4") (pinfunction "GND_4") (pintype "unspecified"))
    )
    (net (code "126") (name "unconnected-(U3-OUT--Pad3)") (class "Default")
      (node (ref "U3") (pin "3") (pinfunction "OUT-_3") (pintype "unspecified"))
    )
    (net (code "127") (name "unconnected-(U4-EN-Pad6)") (class "Default")
      (node (ref "U4") (pin "6") (pinfunction "EN_6") (pintype "unspecified"))
    )
    (net (code "128") (name "unconnected-(U4-Vcc3-Pad1)") (class "Default")
      (node (ref "U4") (pin "1") (pinfunction "Vcc3_1") (pintype "unspecified"))
    )
    (net (code "129") (name "unconnected-(U5-EEP-Pad12)") (class "Default")
      (node (ref "U5") (pin "12") (pinfunction "EEP_12") (pintype "unspecified"))
    )
    (net (code "130") (name "unconnected-(U5-ULT-Pad7)") (class "Default")
      (node (ref "U5") (pin "7") (pinfunction "ULT_7") (pintype "unspecified"))
    )
  )
)
